# Synth_2.net
KiCad netlist of a schematic drawn in EAGLE
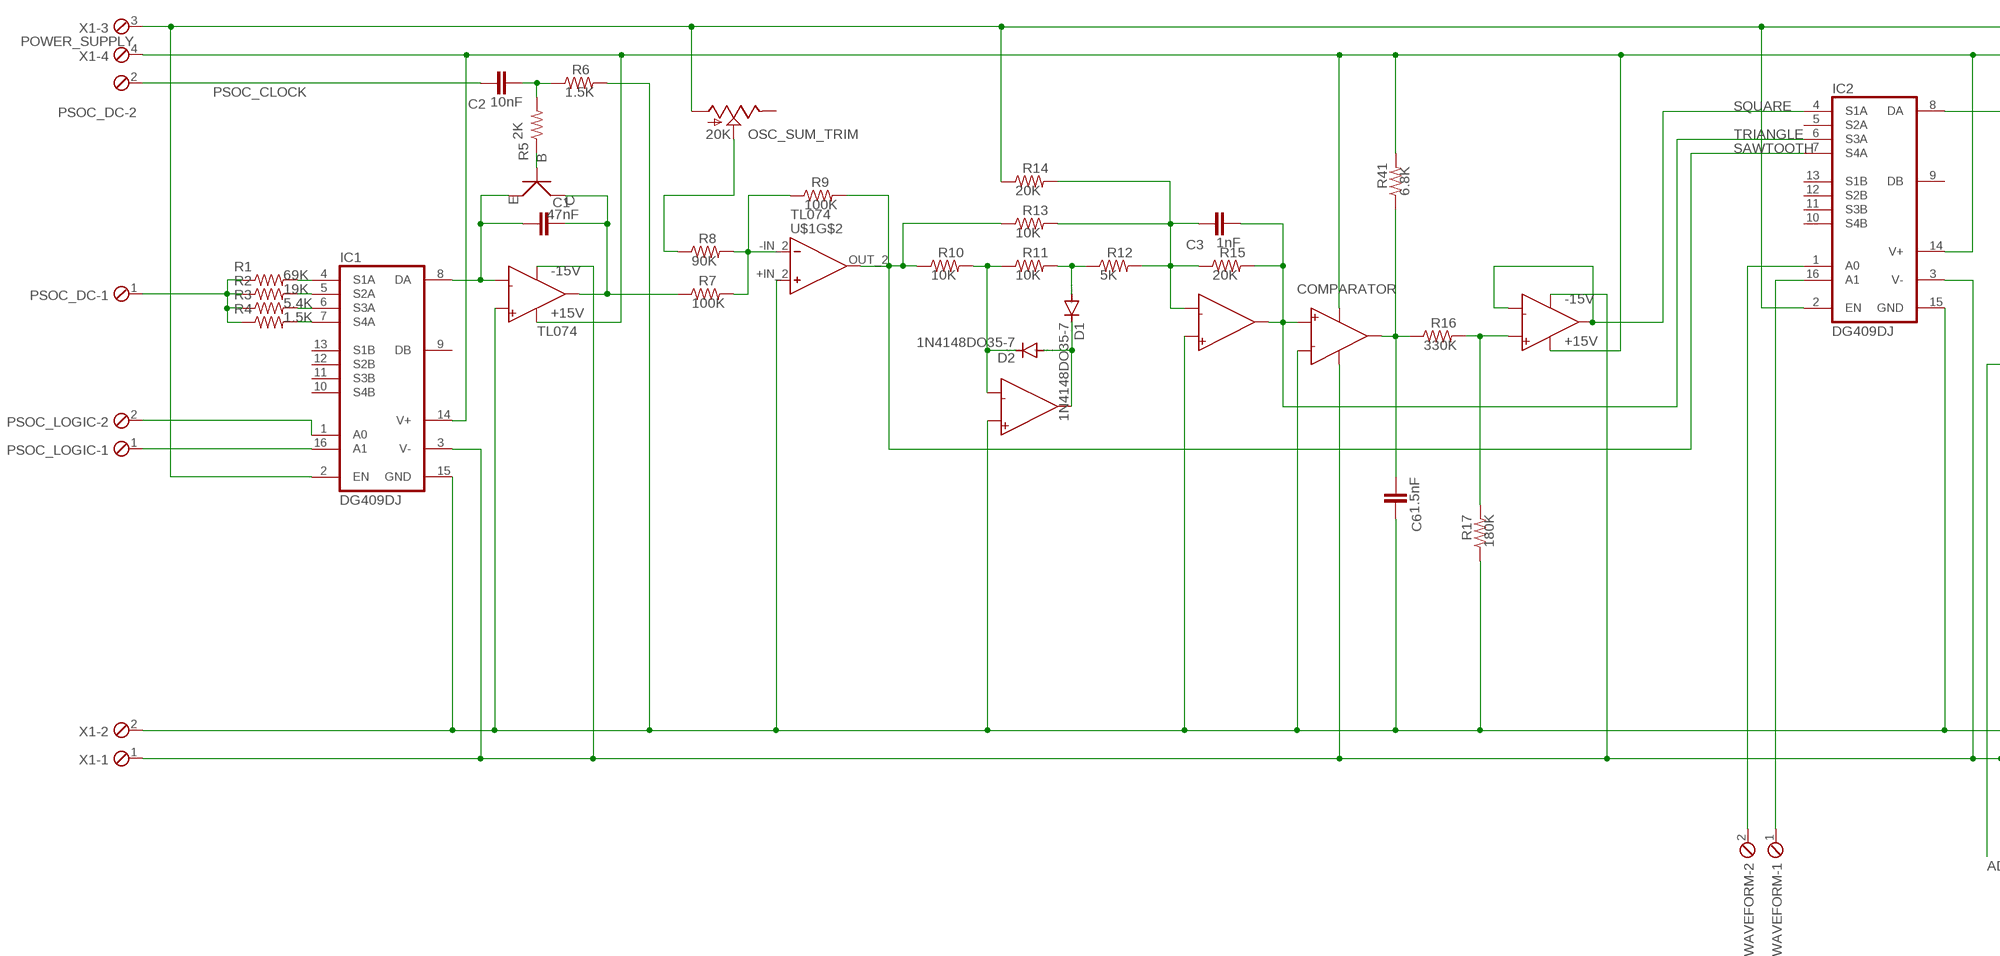
[diagram p0: schematic, sheet 1, part 1 of 2]
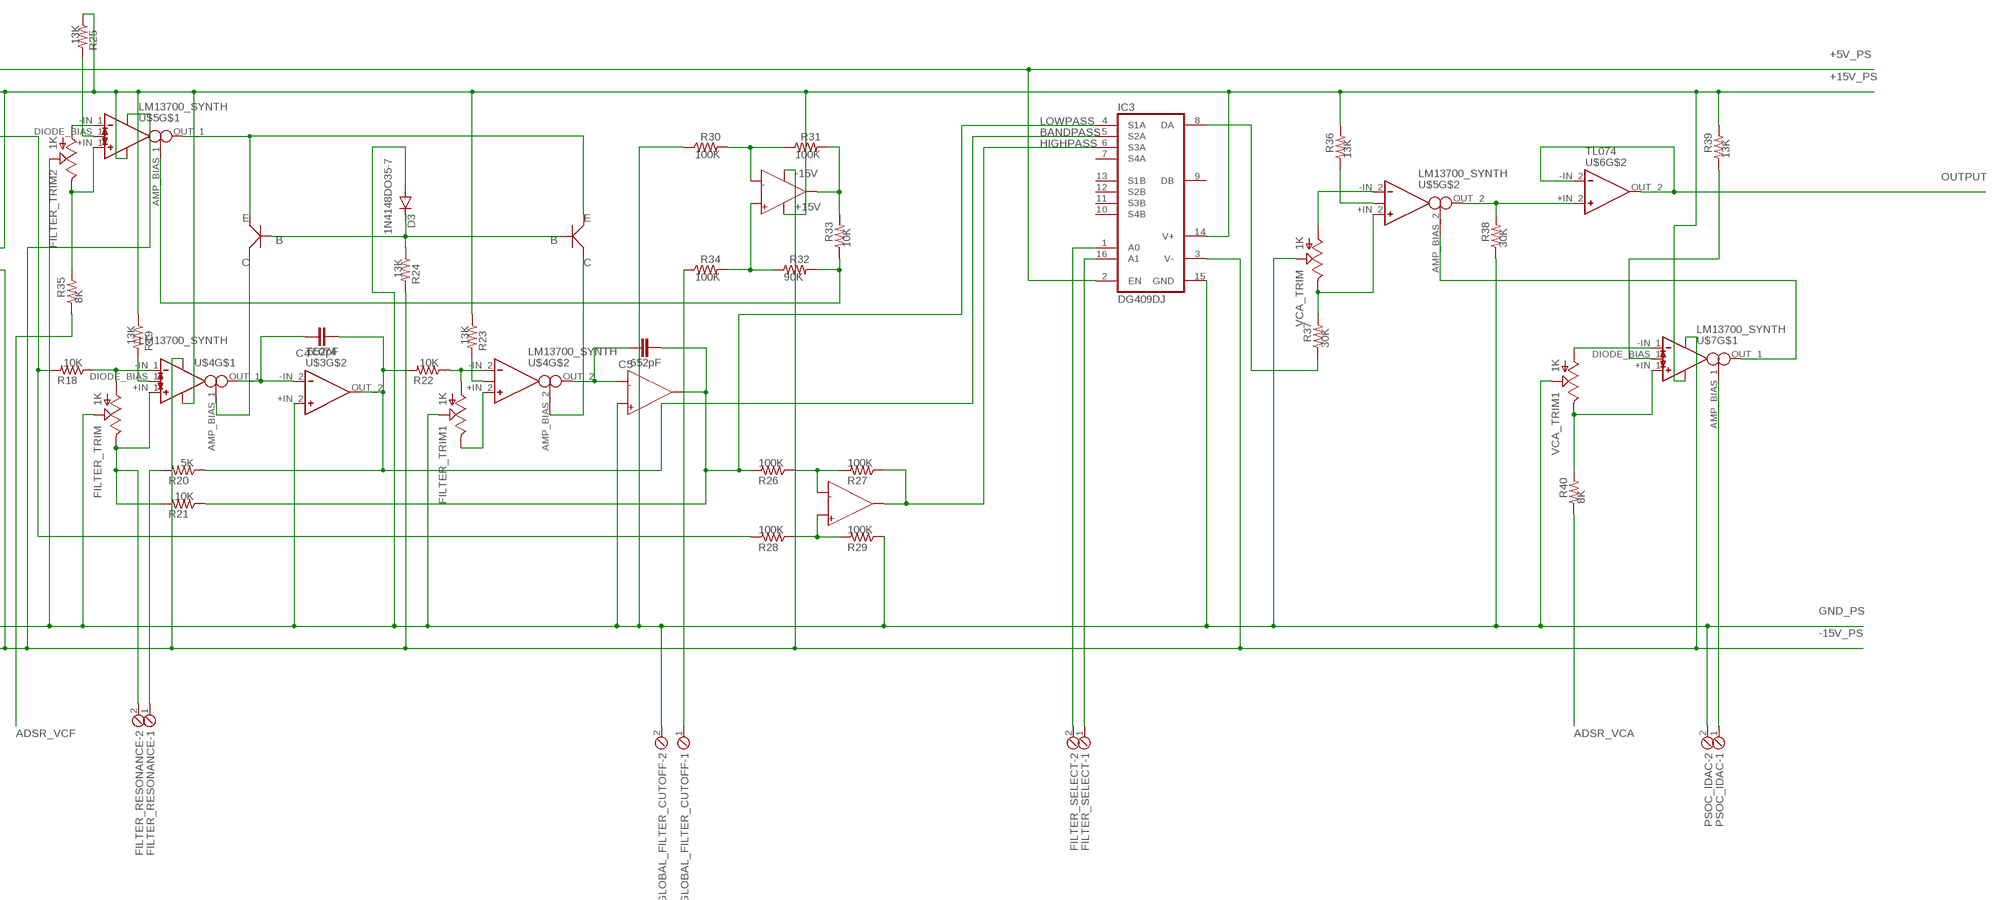
[diagram p1: schematic, sheet 1, part 2 of 2]

(export (version "E")
  (design (tool "Eeschema 10.0.6"))
  (components
    (comp (ref "C1")
      (value "C-EU025-024X044")
      (footprint "eagle-import:C025-024X044")
      (fields (field (name "SPICEPREFIX") "C") (field (name "SPICEPREFIX_1") "47nF"))
      (libsource (lib "eagle-import") (part "C-EU025-024X044"))
    )
    (comp (ref "C2")
      (value "C-EU025-024X044")
      (footprint "eagle-import:C025-024X044")
      (fields (field (name "SPICEPREFIX") "C") (field (name "SPICEPREFIX_1") "10nF"))
      (libsource (lib "eagle-import") (part "C-EU025-024X044"))
    )
    (comp (ref "C3")
      (value "C-EU025-024X044")
      (footprint "eagle-import:C025-024X044")
      (fields (field (name "SPICEPREFIX") "C") (field (name "SPICEPREFIX_1") "1nF"))
      (libsource (lib "eagle-import") (part "C-EU025-024X044"))
    )
    (comp (ref "C4")
      (value "C-EU025-024X044")
      (footprint "eagle-import:C025-024X044")
      (fields (field (name "SPICEPREFIX") "C") (field (name "SPICEPREFIX_1") "652pF"))
      (libsource (lib "eagle-import") (part "C-EU025-024X044"))
    )
    (comp (ref "C5")
      (value "C-EU025-024X044")
      (footprint "eagle-import:C025-024X044")
      (fields (field (name "SPICEPREFIX") "C") (field (name "SPICEPREFIX_1") "652pF"))
      (libsource (lib "eagle-import") (part "C-EU025-024X044"))
    )
    (comp (ref "C6")
      (value "C-EU025-024X044")
      (footprint "eagle-import:C025-024X044")
      (fields (field (name "SPICEPREFIX") "C") (field (name "SPICEPREFIX_1") "1.5nF"))
      (libsource (lib "eagle-import") (part "C-EU025-024X044"))
    )
    (comp (ref "D1")
      (value "1N4148DO35-7")
      (footprint "eagle-import:DO35-7")
      (libsource (lib "eagle-import") (part "1N4148DO35-7"))
    )
    (comp (ref "D2")
      (value "1N4148DO35-7")
      (footprint "eagle-import:DO35-7")
      (libsource (lib "eagle-import") (part "1N4148DO35-7"))
    )
    (comp (ref "D3")
      (value "1N4148DO35-7")
      (footprint "eagle-import:DO35-7")
      (libsource (lib "eagle-import") (part "1N4148DO35-7"))
    )
    (comp (ref "FILTER_RESONANCE")
      (value "MPT2")
      (footprint "eagle-import:2POL254")
      (libsource (lib "eagle-import") (part "MPT2"))
    )
    (comp (ref "FILTER_SELECT")
      (value "MPT2")
      (footprint "eagle-import:2POL254")
      (libsource (lib "eagle-import") (part "MPT2"))
    )
    (comp (ref "FILTER_TRIM")
      (value "TRIM_US-CT6")
      (footprint "eagle-import:CT6")
      (fields (field (name "POPULARITY") "2") (field (name "POPULARITY_1") "1K"))
      (libsource (lib "eagle-import") (part "TRIM_US-CT6"))
    )
    (comp (ref "FILTER_TRIM1")
      (value "TRIM_US-CT6")
      (footprint "eagle-import:CT6")
      (fields (field (name "POPULARITY") "2") (field (name "POPULARITY_1") "1K"))
      (libsource (lib "eagle-import") (part "TRIM_US-CT6"))
    )
    (comp (ref "FILTER_TRIM2")
      (value "TRIM_US-CT6")
      (footprint "eagle-import:CT6")
      (fields (field (name "POPULARITY") "2") (field (name "POPULARITY_1") "1K"))
      (libsource (lib "eagle-import") (part "TRIM_US-CT6"))
    )
    (comp (ref "GLOBAL_FILTER_CUTOFF")
      (value "MPT2")
      (footprint "eagle-import:2POL254")
      (libsource (lib "eagle-import") (part "MPT2"))
    )
    (comp (ref "IC1")
      (value "DG409DJ")
      (footprint "eagle-import:DIL16")
      (fields (field (name "MF") "INTERSIL"))
      (libsource (lib "eagle-import") (part "DG409DJ"))
    )
    (comp (ref "IC2")
      (value "DG409DJ")
      (footprint "eagle-import:DIL16")
      (fields (field (name "MF") "INTERSIL"))
      (libsource (lib "eagle-import") (part "DG409DJ"))
    )
    (comp (ref "IC3")
      (value "DG409DJ")
      (footprint "eagle-import:DIL16")
      (fields (field (name "MF") "INTERSIL"))
      (libsource (lib "eagle-import") (part "DG409DJ"))
    )
    (comp (ref "LM293")
      (value "LM293")
      (footprint "eagle-import:LM293")
      (libsource (lib "eagle-import") (part "LM293"))
    )
    (comp (ref "OSC_SUM_TRIM")
      (value "TRIM_US-CT6")
      (footprint "eagle-import:CT6")
      (fields (field (name "POPULARITY") "2") (field (name "POPULARITY_1") "20K"))
      (libsource (lib "eagle-import") (part "TRIM_US-CT6"))
    )
    (comp (ref "PSOC_DC")
      (value "MPT2")
      (footprint "eagle-import:2POL254")
      (libsource (lib "eagle-import") (part "MPT2"))
    )
    (comp (ref "PSOC_IDAC")
      (value "MPT2")
      (footprint "eagle-import:2POL254")
      (libsource (lib "eagle-import") (part "MPT2"))
    )
    (comp (ref "PSOC_LOGIC")
      (value "MPT2")
      (footprint "eagle-import:2POL254")
      (libsource (lib "eagle-import") (part "MPT2"))
    )
    (comp (ref "R1")
      (value "R-US_0204/7")
      (footprint "eagle-import:0204_7")
      (fields (field (name "SPICEPREFIX") "R") (field (name "SPICEPREFIX_1") "69K"))
      (libsource (lib "eagle-import") (part "R-US_0204/7"))
    )
    (comp (ref "R2")
      (value "R-US_0204/7")
      (footprint "eagle-import:0204_7")
      (fields (field (name "SPICEPREFIX") "R") (field (name "SPICEPREFIX_1") "19K"))
      (libsource (lib "eagle-import") (part "R-US_0204/7"))
    )
    (comp (ref "R3")
      (value "R-US_0204/7")
      (footprint "eagle-import:0204_7")
      (fields (field (name "SPICEPREFIX") "R") (field (name "SPICEPREFIX_1") "5.4K"))
      (libsource (lib "eagle-import") (part "R-US_0204/7"))
    )
    (comp (ref "R4")
      (value "R-US_0204/7")
      (footprint "eagle-import:0204_7")
      (fields (field (name "SPICEPREFIX") "R") (field (name "SPICEPREFIX_1") "1.5K"))
      (libsource (lib "eagle-import") (part "R-US_0204/7"))
    )
    (comp (ref "R5")
      (value "R-US_0204/7")
      (footprint "eagle-import:0204_7")
      (fields (field (name "SPICEPREFIX") "R") (field (name "SPICEPREFIX_1") "2K"))
      (libsource (lib "eagle-import") (part "R-US_0204/7"))
    )
    (comp (ref "R6")
      (value "R-US_0204/7")
      (footprint "eagle-import:0204_7")
      (fields (field (name "SPICEPREFIX") "R") (field (name "SPICEPREFIX_1") "1.5K"))
      (libsource (lib "eagle-import") (part "R-US_0204/7"))
    )
    (comp (ref "R7")
      (value "R-US_0204/7")
      (footprint "eagle-import:0204_7")
      (fields (field (name "SPICEPREFIX") "R") (field (name "SPICEPREFIX_1") "100K"))
      (libsource (lib "eagle-import") (part "R-US_0204/7"))
    )
    (comp (ref "R8")
      (value "R-US_0204/7")
      (footprint "eagle-import:0204_7")
      (fields (field (name "SPICEPREFIX") "R") (field (name "SPICEPREFIX_1") "90K"))
      (libsource (lib "eagle-import") (part "R-US_0204/7"))
    )
    (comp (ref "R9")
      (value "R-US_0204/7")
      (footprint "eagle-import:0204_7")
      (fields (field (name "SPICEPREFIX") "R") (field (name "SPICEPREFIX_1") "100K"))
      (libsource (lib "eagle-import") (part "R-US_0204/7"))
    )
    (comp (ref "R10")
      (value "R-US_0204/7")
      (footprint "eagle-import:0204_7")
      (fields (field (name "SPICEPREFIX") "R") (field (name "SPICEPREFIX_1") "10K"))
      (libsource (lib "eagle-import") (part "R-US_0204/7"))
    )
    (comp (ref "R11")
      (value "R-US_0204/7")
      (footprint "eagle-import:0204_7")
      (fields (field (name "SPICEPREFIX") "R") (field (name "SPICEPREFIX_1") "10K"))
      (libsource (lib "eagle-import") (part "R-US_0204/7"))
    )
    (comp (ref "R12")
      (value "R-US_0204/7")
      (footprint "eagle-import:0204_7")
      (fields (field (name "SPICEPREFIX") "R") (field (name "SPICEPREFIX_1") "5K"))
      (libsource (lib "eagle-import") (part "R-US_0204/7"))
    )
    (comp (ref "R13")
      (value "R-US_0204/7")
      (footprint "eagle-import:0204_7")
      (fields (field (name "SPICEPREFIX") "R") (field (name "SPICEPREFIX_1") "10K"))
      (libsource (lib "eagle-import") (part "R-US_0204/7"))
    )
    (comp (ref "R14")
      (value "R-US_0204/7")
      (footprint "eagle-import:0204_7")
      (fields (field (name "SPICEPREFIX") "R") (field (name "SPICEPREFIX_1") "20K"))
      (libsource (lib "eagle-import") (part "R-US_0204/7"))
    )
    (comp (ref "R15")
      (value "R-US_0204/7")
      (footprint "eagle-import:0204_7")
      (fields (field (name "SPICEPREFIX") "R") (field (name "SPICEPREFIX_1") "20K"))
      (libsource (lib "eagle-import") (part "R-US_0204/7"))
    )
    (comp (ref "R16")
      (value "R-US_0204/7")
      (footprint "eagle-import:0204_7")
      (fields (field (name "SPICEPREFIX") "R") (field (name "SPICEPREFIX_1") "330K"))
      (libsource (lib "eagle-import") (part "R-US_0204/7"))
    )
    (comp (ref "R17")
      (value "R-US_0204/7")
      (footprint "eagle-import:0204_7")
      (fields (field (name "SPICEPREFIX") "R") (field (name "SPICEPREFIX_1") "180K"))
      (libsource (lib "eagle-import") (part "R-US_0204/7"))
    )
    (comp (ref "R18")
      (value "R-US_0204/7")
      (footprint "eagle-import:0204_7")
      (fields (field (name "SPICEPREFIX") "R") (field (name "SPICEPREFIX_1") "10K"))
      (libsource (lib "eagle-import") (part "R-US_0204/7"))
    )
    (comp (ref "R19")
      (value "R-US_0204/7")
      (footprint "eagle-import:0204_7")
      (fields (field (name "SPICEPREFIX") "R") (field (name "SPICEPREFIX_1") "13K"))
      (libsource (lib "eagle-import") (part "R-US_0204/7"))
    )
    (comp (ref "R20")
      (value "R-US_0204/7")
      (footprint "eagle-import:0204_7")
      (fields (field (name "SPICEPREFIX") "R") (field (name "SPICEPREFIX_1") "5K"))
      (libsource (lib "eagle-import") (part "R-US_0204/7"))
    )
    (comp (ref "R21")
      (value "R-US_0204/7")
      (footprint "eagle-import:0204_7")
      (fields (field (name "SPICEPREFIX") "R") (field (name "SPICEPREFIX_1") "10K"))
      (libsource (lib "eagle-import") (part "R-US_0204/7"))
    )
    (comp (ref "R22")
      (value "R-US_0204/7")
      (footprint "eagle-import:0204_7")
      (fields (field (name "SPICEPREFIX") "R") (field (name "SPICEPREFIX_1") "10K"))
      (libsource (lib "eagle-import") (part "R-US_0204/7"))
    )
    (comp (ref "R23")
      (value "R-US_0204/7")
      (footprint "eagle-import:0204_7")
      (fields (field (name "SPICEPREFIX") "R") (field (name "SPICEPREFIX_1") "13K"))
      (libsource (lib "eagle-import") (part "R-US_0204/7"))
    )
    (comp (ref "R24")
      (value "R-US_0204/7")
      (footprint "eagle-import:0204_7")
      (fields (field (name "SPICEPREFIX") "R") (field (name "SPICEPREFIX_1") "13K"))
      (libsource (lib "eagle-import") (part "R-US_0204/7"))
    )
    (comp (ref "R25")
      (value "R-US_0204/7")
      (footprint "eagle-import:0204_7")
      (fields (field (name "SPICEPREFIX") "R") (field (name "SPICEPREFIX_1") "13K"))
      (libsource (lib "eagle-import") (part "R-US_0204/7"))
    )
    (comp (ref "R26")
      (value "R-US_0204/7")
      (footprint "eagle-import:0204_7")
      (fields (field (name "SPICEPREFIX") "R") (field (name "SPICEPREFIX_1") "100K"))
      (libsource (lib "eagle-import") (part "R-US_0204/7"))
    )
    (comp (ref "R27")
      (value "R-US_0204/7")
      (footprint "eagle-import:0204_7")
      (fields (field (name "SPICEPREFIX") "R") (field (name "SPICEPREFIX_1") "100K"))
      (libsource (lib "eagle-import") (part "R-US_0204/7"))
    )
    (comp (ref "R28")
      (value "R-US_0204/7")
      (footprint "eagle-import:0204_7")
      (fields (field (name "SPICEPREFIX") "R") (field (name "SPICEPREFIX_1") "100K"))
      (libsource (lib "eagle-import") (part "R-US_0204/7"))
    )
    (comp (ref "R29")
      (value "R-US_0204/7")
      (footprint "eagle-import:0204_7")
      (fields (field (name "SPICEPREFIX") "R") (field (name "SPICEPREFIX_1") "100K"))
      (libsource (lib "eagle-import") (part "R-US_0204/7"))
    )
    (comp (ref "R30")
      (value "R-US_0204/7")
      (footprint "eagle-import:0204_7")
      (fields (field (name "SPICEPREFIX") "R") (field (name "SPICEPREFIX_1") "100K"))
      (libsource (lib "eagle-import") (part "R-US_0204/7"))
    )
    (comp (ref "R31")
      (value "R-US_0204/7")
      (footprint "eagle-import:0204_7")
      (fields (field (name "SPICEPREFIX") "R") (field (name "SPICEPREFIX_1") "100K"))
      (libsource (lib "eagle-import") (part "R-US_0204/7"))
    )
    (comp (ref "R32")
      (value "R-US_0204/7")
      (footprint "eagle-import:0204_7")
      (fields (field (name "SPICEPREFIX") "R") (field (name "SPICEPREFIX_1") "90K"))
      (libsource (lib "eagle-import") (part "R-US_0204/7"))
    )
    (comp (ref "R33")
      (value "R-US_0204/7")
      (footprint "eagle-import:0204_7")
      (fields (field (name "SPICEPREFIX") "R") (field (name "SPICEPREFIX_1") "10K"))
      (libsource (lib "eagle-import") (part "R-US_0204/7"))
    )
    (comp (ref "R34")
      (value "R-US_0204/7")
      (footprint "eagle-import:0204_7")
      (fields (field (name "SPICEPREFIX") "R") (field (name "SPICEPREFIX_1") "100K"))
      (libsource (lib "eagle-import") (part "R-US_0204/7"))
    )
    (comp (ref "R35")
      (value "R-US_0204/7")
      (footprint "eagle-import:0204_7")
      (fields (field (name "SPICEPREFIX") "R") (field (name "SPICEPREFIX_1") "8K"))
      (libsource (lib "eagle-import") (part "R-US_0204/7"))
    )
    (comp (ref "R36")
      (value "R-US_0204/7")
      (footprint "eagle-import:0204_7")
      (fields (field (name "SPICEPREFIX") "R") (field (name "SPICEPREFIX_1") "13K"))
      (libsource (lib "eagle-import") (part "R-US_0204/7"))
    )
    (comp (ref "R37")
      (value "R-US_0204/7")
      (footprint "eagle-import:0204_7")
      (fields (field (name "SPICEPREFIX") "R") (field (name "SPICEPREFIX_1") "30K"))
      (libsource (lib "eagle-import") (part "R-US_0204/7"))
    )
    (comp (ref "R38")
      (value "R-US_0204/7")
      (footprint "eagle-import:0204_7")
      (fields (field (name "SPICEPREFIX") "R") (field (name "SPICEPREFIX_1") "30K"))
      (libsource (lib "eagle-import") (part "R-US_0204/7"))
    )
    (comp (ref "R39")
      (value "R-US_0204/7")
      (footprint "eagle-import:0204_7")
      (fields (field (name "SPICEPREFIX") "R") (field (name "SPICEPREFIX_1") "13K"))
      (libsource (lib "eagle-import") (part "R-US_0204/7"))
    )
    (comp (ref "R40")
      (value "R-US_0204/7")
      (footprint "eagle-import:0204_7")
      (fields (field (name "SPICEPREFIX") "R") (field (name "SPICEPREFIX_1") "8K"))
      (libsource (lib "eagle-import") (part "R-US_0204/7"))
    )
    (comp (ref "R41")
      (value "R-US_0204/7")
      (footprint "eagle-import:0204_7")
      (fields (field (name "SPICEPREFIX") "R") (field (name "SPICEPREFIX_1") "6.8K"))
      (libsource (lib "eagle-import") (part "R-US_0204/7"))
    )
    (comp (ref "U$1")
      (value "TL074")
      (footprint "eagle-import:TL074")
      (libsource (lib "eagle-import") (part "TL074"))
    )
    (comp (ref "U$2")
      (value "MPQ2907A")
      (footprint "eagle-import:MPQ2907A")
      (libsource (lib "eagle-import") (part "MPQ2907A"))
    )
    (comp (ref "U$3")
      (value "TL074")
      (footprint "eagle-import:TL074")
      (libsource (lib "eagle-import") (part "TL074"))
    )
    (comp (ref "U$4")
      (value "LM13700_SYNTH")
      (footprint "eagle-import:LM13700_SYNTH")
      (libsource (lib "eagle-import") (part "LM13700_SYNTH"))
    )
    (comp (ref "U$5")
      (value "LM13700_SYNTH")
      (footprint "eagle-import:LM13700_SYNTH")
      (libsource (lib "eagle-import") (part "LM13700_SYNTH"))
    )
    (comp (ref "U$6")
      (value "TL074")
      (footprint "eagle-import:TL074")
      (libsource (lib "eagle-import") (part "TL074"))
    )
    (comp (ref "U$7")
      (value "LM13700_SYNTH")
      (footprint "eagle-import:LM13700_SYNTH")
      (libsource (lib "eagle-import") (part "LM13700_SYNTH"))
    )
    (comp (ref "VCA_TRIM")
      (value "TRIM_US-CT6")
      (footprint "eagle-import:CT6")
      (fields (field (name "POPULARITY") "2") (field (name "POPULARITY_1") "1K"))
      (libsource (lib "eagle-import") (part "TRIM_US-CT6"))
    )
    (comp (ref "VCA_TRIM1")
      (value "TRIM_US-CT6")
      (footprint "eagle-import:CT6")
      (fields (field (name "POPULARITY") "2") (field (name "POPULARITY_1") "1K"))
      (libsource (lib "eagle-import") (part "TRIM_US-CT6"))
    )
    (comp (ref "WAVEFORM")
      (value "MPT2")
      (footprint "eagle-import:2POL254")
      (libsource (lib "eagle-import") (part "MPT2"))
    )
    (comp (ref "X1")
      (value "POWER_SUPPLY")
      (footprint "eagle-import:4POL254")
      (libsource (lib "eagle-import") (part "MPT4"))
    )
  )
  (nets
    (net (code "1") (name "/+5V_PS") (class "Default")
      (node (ref "IC1") (pin "2") (pinfunction "EN_2") (pintype "input"))
      (node (ref "IC2") (pin "2") (pinfunction "EN_2") (pintype "input"))
      (node (ref "IC3") (pin "2") (pinfunction "EN_2") (pintype "input"))
      (node (ref "OSC_SUM_TRIM") (pin "A") (pinfunction "A_A") (pintype "passive"))
      (node (ref "R14") (pin "1") (pinfunction "1_1") (pintype "passive"))
      (node (ref "X1") (pin "3") (pinfunction "1_3") (pintype "passive"))
    )
    (net (code "2") (name "/+15V_PS") (class "Default")
      (node (ref "IC1") (pin "14") (pinfunction "V+_14") (pintype "power_in"))
      (node (ref "IC2") (pin "14") (pinfunction "V+_14") (pintype "power_in"))
      (node (ref "IC3") (pin "14") (pinfunction "V+_14") (pintype "power_in"))
      (node (ref "LM293") (pin "VCC") (pinfunction "VCC_VCC") (pintype "power_in"))
      (node (ref "R19") (pin "1") (pinfunction "1_1") (pintype "passive"))
      (node (ref "R23") (pin "1") (pinfunction "1_1") (pintype "passive"))
      (node (ref "R25") (pin "1") (pinfunction "1_1") (pintype "passive"))
      (node (ref "R36") (pin "2") (pinfunction "2_2") (pintype "passive"))
      (node (ref "R39") (pin "2") (pinfunction "2_2") (pintype "passive"))
      (node (ref "R41") (pin "2") (pinfunction "2_2") (pintype "passive"))
      (node (ref "U$1") (pin "VCC+") (pinfunction "VCC+_VCC+") (pintype "power_in"))
      (node (ref "U$3") (pin "VCC+") (pinfunction "VCC+_VCC+") (pintype "power_in"))
      (node (ref "U$4") (pin "+V") (pinfunction "+V_+V") (pintype "power_in"))
      (node (ref "U$5") (pin "+V") (pinfunction "+V_+V") (pintype "power_in"))
      (node (ref "U$6") (pin "VCC+") (pinfunction "VCC+_VCC+") (pintype "power_in"))
      (node (ref "U$7") (pin "+V") (pinfunction "+V_+V") (pintype "power_in"))
      (node (ref "X1") (pin "4") (pinfunction "1_4") (pintype "passive"))
    )
    (net (code "3") (name "/-15V_PS") (class "Default")
      (node (ref "IC1") (pin "3") (pinfunction "V-_3") (pintype "power_in"))
      (node (ref "IC2") (pin "3") (pinfunction "V-_3") (pintype "power_in"))
      (node (ref "IC3") (pin "3") (pinfunction "V-_3") (pintype "power_in"))
      (node (ref "LM293") (pin "GND") (pinfunction "GND_GND") (pintype "input"))
      (node (ref "R24") (pin "2") (pinfunction "2_2") (pintype "passive"))
      (node (ref "U$1") (pin "VCC-") (pinfunction "VCC-_VCC-") (pintype "power_in"))
      (node (ref "U$3") (pin "VCC-") (pinfunction "VCC-_VCC-") (pintype "power_in"))
      (node (ref "U$4") (pin "-V") (pinfunction "-V_-V") (pintype "power_in"))
      (node (ref "U$5") (pin "-V") (pinfunction "-V_-V") (pintype "power_in"))
      (node (ref "U$6") (pin "VCC-") (pinfunction "VCC-_VCC-") (pintype "power_in"))
      (node (ref "U$7") (pin "-V") (pinfunction "-V_-V") (pintype "power_in"))
      (node (ref "X1") (pin "1") (pinfunction "1_1") (pintype "passive"))
    )
    (net (code "4") (name "/ADSR_VCA") (class "Default")
      (node (ref "R40") (pin "2") (pinfunction "2_2") (pintype "passive"))
      (node (ref "U$7") (pin "+IN_1") (pinfunction "+IN_1_+IN_1") (pintype "input"))
      (node (ref "VCA_TRIM1") (pin "E") (pinfunction "E_E") (pintype "passive"))
    )
    (net (code "5") (name "/ADSR_VCF") (class "Default")
      (node (ref "R35") (pin "1") (pinfunction "1_1") (pintype "passive"))
    )
    (net (code "6") (name "/BANDPASS") (class "Default")
      (node (ref "C4") (pin "2") (pinfunction "2_2") (pintype "passive"))
      (node (ref "IC3") (pin "5") (pinfunction "S2A_5") (pintype "passive"))
      (node (ref "R20") (pin "1") (pinfunction "1_1") (pintype "passive"))
      (node (ref "R22") (pin "2") (pinfunction "2_2") (pintype "passive"))
      (node (ref "U$3") (pin "OUT_2") (pinfunction "OUT_2_OUT_2") (pintype "output"))
    )
    (net (code "7") (name "/COMPARATOR") (class "Default")
      (node (ref "C6") (pin "2") (pinfunction "2_2") (pintype "passive"))
      (node (ref "LM293") (pin "OUT_1") (pinfunction "OUT_1_OUT_1") (pintype "output"))
      (node (ref "R16") (pin "1") (pinfunction "1_1") (pintype "passive"))
      (node (ref "R41") (pin "1") (pinfunction "1_1") (pintype "passive"))
    )
    (net (code "8") (name "/GND_PS") (class "Default")
      (node (ref "C6") (pin "1") (pinfunction "1_1") (pintype "passive"))
      (node (ref "D3") (pin "A") (pinfunction "A_A") (pintype "passive"))
      (node (ref "FILTER_TRIM") (pin "S") (pinfunction "S_S") (pintype "passive"))
      (node (ref "FILTER_TRIM1") (pin "S") (pinfunction "S_S") (pintype "passive"))
      (node (ref "FILTER_TRIM2") (pin "S") (pinfunction "S_S") (pintype "passive"))
      (node (ref "GLOBAL_FILTER_CUTOFF") (pin "2") (pinfunction "1_2") (pintype "passive"))
      (node (ref "IC1") (pin "15") (pinfunction "GND_15") (pintype "power_in"))
      (node (ref "IC2") (pin "15") (pinfunction "GND_15") (pintype "power_in"))
      (node (ref "IC3") (pin "15") (pinfunction "GND_15") (pintype "power_in"))
      (node (ref "LM293") (pin "-IN_1") (pinfunction "-IN_1_-IN_1") (pintype "input"))
      (node (ref "PSOC_IDAC") (pin "2") (pinfunction "1_2") (pintype "passive"))
      (node (ref "R17") (pin "1") (pinfunction "1_1") (pintype "passive"))
      (node (ref "R29") (pin "1") (pinfunction "1_1") (pintype "passive"))
      (node (ref "R30") (pin "1") (pinfunction "1_1") (pintype "passive"))
      (node (ref "R38") (pin "1") (pinfunction "1_1") (pintype "passive"))
      (node (ref "R6") (pin "2") (pinfunction "2_2") (pintype "passive"))
      (node (ref "U$1") (pin "+IN_1") (pinfunction "+IN_1_+IN_1") (pintype "input"))
      (node (ref "U$1") (pin "+IN_2") (pinfunction "+IN_2_+IN_2") (pintype "input"))
      (node (ref "U$1") (pin "+IN_3") (pinfunction "+IN_3_+IN_3") (pintype "input"))
      (node (ref "U$1") (pin "+IN_4") (pinfunction "+IN_4_+IN_4") (pintype "input"))
      (node (ref "U$3") (pin "+IN_2") (pinfunction "+IN_2_+IN_2") (pintype "input"))
      (node (ref "U$3") (pin "+IN_4") (pinfunction "+IN_4_+IN_4") (pintype "input"))
      (node (ref "VCA_TRIM") (pin "S") (pinfunction "S_S") (pintype "passive"))
      (node (ref "VCA_TRIM1") (pin "S") (pinfunction "S_S") (pintype "passive"))
      (node (ref "X1") (pin "2") (pinfunction "1_2") (pintype "passive"))
    )
    (net (code "9") (name "/HIGHPASS") (class "Default")
      (node (ref "IC3") (pin "6") (pinfunction "S3A_6") (pintype "passive"))
      (node (ref "R27") (pin "1") (pinfunction "1_1") (pintype "passive"))
      (node (ref "U$3") (pin "OUT_3") (pinfunction "OUT_3_OUT_3") (pintype "output"))
    )
    (net (code "10") (name "/LOWPASS") (class "Default")
      (node (ref "C5") (pin "2") (pinfunction "2_2") (pintype "passive"))
      (node (ref "IC3") (pin "4") (pinfunction "S1A_4") (pintype "passive"))
      (node (ref "R21") (pin "1") (pinfunction "1_1") (pintype "passive"))
      (node (ref "R26") (pin "2") (pinfunction "2_2") (pintype "passive"))
      (node (ref "U$3") (pin "OUT_4") (pinfunction "OUT_4_OUT_4") (pintype "input"))
    )
    (net (code "11") (name "/OUTPUT") (class "Default")
      (node (ref "U$6") (pin "-IN_2") (pinfunction "-IN_2_-IN_2") (pintype "input"))
      (node (ref "U$6") (pin "OUT_2") (pinfunction "OUT_2_OUT_2") (pintype "output"))
    )
    (net (code "12") (name "/PSOC_CLOCK") (class "Default")
      (node (ref "C2") (pin "1") (pinfunction "1_1") (pintype "passive"))
      (node (ref "PSOC_DC") (pin "2") (pinfunction "1_2") (pintype "passive"))
    )
    (net (code "13") (name "/SAWTOOTH") (class "Default")
      (node (ref "IC2") (pin "7") (pinfunction "S4A_7") (pintype "passive"))
      (node (ref "R10") (pin "1") (pinfunction "1_1") (pintype "passive"))
      (node (ref "R13") (pin "1") (pinfunction "1_1") (pintype "passive"))
      (node (ref "R9") (pin "2") (pinfunction "2_2") (pintype "passive"))
      (node (ref "U$1") (pin "OUT_2") (pinfunction "OUT_2_OUT_2") (pintype "output"))
    )
    (net (code "14") (name "/SQUARE") (class "Default")
      (node (ref "IC2") (pin "4") (pinfunction "S1A_4") (pintype "passive"))
      (node (ref "U$3") (pin "-IN_1") (pinfunction "-IN_1_-IN_1") (pintype "input"))
      (node (ref "U$3") (pin "OUT_1") (pinfunction "OUT_1_OUT_1") (pintype "output"))
    )
    (net (code "15") (name "/TL074") (class "Default")
      (node (ref "C1") (pin "1") (pinfunction "1_1") (pintype "passive"))
      (node (ref "IC1") (pin "8") (pinfunction "DA_8") (pintype "passive"))
      (node (ref "U$1") (pin "-IN_1") (pinfunction "-IN_1_-IN_1") (pintype "input"))
      (node (ref "U$2") (pin "Q1_E") (pinfunction "E_Q1_E") (pintype "bidirectional"))
    )
    (net (code "16") (name "/TRIANGLE") (class "Default")
      (node (ref "C3") (pin "2") (pinfunction "2_2") (pintype "passive"))
      (node (ref "IC2") (pin "6") (pinfunction "S3A_6") (pintype "passive"))
      (node (ref "LM293") (pin "+IN_1") (pinfunction "+IN_1_+IN_1") (pintype "input"))
      (node (ref "R15") (pin "2") (pinfunction "2_2") (pintype "passive"))
      (node (ref "U$1") (pin "OUT_4") (pinfunction "OUT_4_OUT_4") (pintype "input"))
    )
    (net (code "17") (name "Net-(C2-Pad2)") (class "Default")
      (node (ref "C2") (pin "2") (pinfunction "2_2") (pintype "passive"))
      (node (ref "R5") (pin "2") (pinfunction "2_2") (pintype "passive"))
      (node (ref "R6") (pin "1") (pinfunction "1_1") (pintype "passive"))
    )
    (net (code "18") (name "Net-(C3-Pad1)") (class "Default")
      (node (ref "C3") (pin "1") (pinfunction "1_1") (pintype "passive"))
      (node (ref "R12") (pin "2") (pinfunction "2_2") (pintype "passive"))
      (node (ref "R13") (pin "2") (pinfunction "2_2") (pintype "passive"))
      (node (ref "R14") (pin "2") (pinfunction "2_2") (pintype "passive"))
      (node (ref "R15") (pin "1") (pinfunction "1_1") (pintype "passive"))
      (node (ref "U$1") (pin "-IN_4") (pinfunction "-IN_4_-IN_4") (pintype "input"))
    )
    (net (code "19") (name "Net-(C4-Pad1)") (class "Default")
      (node (ref "C4") (pin "1") (pinfunction "1_1") (pintype "passive"))
      (node (ref "U$3") (pin "-IN_2") (pinfunction "-IN_2_-IN_2") (pintype "input"))
      (node (ref "U$4") (pin "OUT_1") (pinfunction "OUT_1_OUT_1") (pintype "output"))
    )
    (net (code "20") (name "Net-(C5-Pad1)") (class "Default")
      (node (ref "C5") (pin "1") (pinfunction "1_1") (pintype "passive"))
      (node (ref "U$3") (pin "-IN_4") (pinfunction "-IN_4_-IN_4") (pintype "input"))
      (node (ref "U$4") (pin "OUT_2") (pinfunction "OUT_2_OUT_2") (pintype "output"))
    )
    (net (code "21") (name "Net-(D1-PadA)") (class "Default")
      (node (ref "D1") (pin "A") (pinfunction "A_A") (pintype "passive"))
      (node (ref "R11") (pin "2") (pinfunction "2_2") (pintype "passive"))
      (node (ref "R12") (pin "1") (pinfunction "1_1") (pintype "passive"))
    )
    (net (code "22") (name "Net-(D1-PadC)") (class "Default")
      (node (ref "D1") (pin "C") (pinfunction "C_C") (pintype "passive"))
      (node (ref "D2") (pin "A") (pinfunction "A_A") (pintype "passive"))
      (node (ref "U$1") (pin "OUT_3") (pinfunction "OUT_3_OUT_3") (pintype "output"))
    )
    (net (code "23") (name "Net-(D2-PadC)") (class "Default")
      (node (ref "D2") (pin "C") (pinfunction "C_C") (pintype "passive"))
      (node (ref "R10") (pin "2") (pinfunction "2_2") (pintype "passive"))
      (node (ref "R11") (pin "1") (pinfunction "1_1") (pintype "passive"))
      (node (ref "U$1") (pin "-IN_3") (pinfunction "-IN_3_-IN_3") (pintype "input"))
    )
    (net (code "24") (name "Net-(FILTER_RESONANCE-Pad1)") (class "Default")
      (node (ref "FILTER_RESONANCE") (pin "1") (pinfunction "1_1") (pintype "passive"))
      (node (ref "R20") (pin "2") (pinfunction "2_2") (pintype "passive"))
    )
    (net (code "25") (name "Net-(FILTER_RESONANCEB-1)") (class "Default")
      (node (ref "FILTER_RESONANCE") (pin "2") (pinfunction "1_2") (pintype "passive"))
      (node (ref "FILTER_TRIM") (pin "E") (pinfunction "E_E") (pintype "passive"))
      (node (ref "R21") (pin "2") (pinfunction "2_2") (pintype "passive"))
      (node (ref "U$4") (pin "+IN_1") (pinfunction "+IN_1_+IN_1") (pintype "input"))
    )
    (net (code "26") (name "Net-(FILTER_SELECTB-1)") (class "Default")
      (node (ref "FILTER_SELECT") (pin "2") (pinfunction "1_2") (pintype "passive"))
      (node (ref "IC3") (pin "1") (pinfunction "A0_1") (pintype "input"))
    )
    (net (code "27") (name "Net-(FILTER_TRIM-PadA)") (class "Default")
      (node (ref "FILTER_TRIM") (pin "A") (pinfunction "A_A") (pintype "passive"))
      (node (ref "R18") (pin "1") (pinfunction "1_1") (pintype "passive"))
      (node (ref "U$4") (pin "-IN_1") (pinfunction "-IN_1_-IN_1") (pintype "input"))
    )
    (net (code "28") (name "Net-(FILTER_TRIM1-PadA)") (class "Default")
      (node (ref "FILTER_TRIM1") (pin "A") (pinfunction "A_A") (pintype "passive"))
      (node (ref "R22") (pin "1") (pinfunction "1_1") (pintype "passive"))
      (node (ref "U$4") (pin "-IN_2") (pinfunction "-IN_2_-IN_2") (pintype "input"))
    )
    (net (code "29") (name "Net-(FILTER_TRIM1-PadE)") (class "Default")
      (node (ref "FILTER_TRIM1") (pin "E") (pinfunction "E_E") (pintype "passive"))
      (node (ref "U$4") (pin "+IN_2") (pinfunction "+IN_2_+IN_2") (pintype "input"))
    )
    (net (code "30") (name "Net-(FILTER_TRIM2-PadA)") (class "Default")
      (node (ref "FILTER_TRIM2") (pin "A") (pinfunction "A_A") (pintype "passive"))
      (node (ref "U$5") (pin "-IN_1") (pinfunction "-IN_1_-IN_1") (pintype "input"))
    )
    (net (code "31") (name "Net-(FILTER_TRIM2-PadE)") (class "Default")
      (node (ref "FILTER_TRIM2") (pin "E") (pinfunction "E_E") (pintype "passive"))
      (node (ref "R35") (pin "2") (pinfunction "2_2") (pintype "passive"))
      (node (ref "U$5") (pin "+IN_1") (pinfunction "+IN_1_+IN_1") (pintype "input"))
    )
    (net (code "32") (name "Net-(GLOBAL_FILTER_CUTOFF-Pad1)") (class "Default")
      (node (ref "GLOBAL_FILTER_CUTOFF") (pin "1") (pinfunction "1_1") (pintype "passive"))
      (node (ref "R34") (pin "1") (pinfunction "1_1") (pintype "passive"))
    )
    (net (code "33") (name "Net-(IC1-A0)") (class "Default")
      (node (ref "IC1") (pin "1") (pinfunction "A0_1") (pintype "input"))
      (node (ref "PSOC_LOGIC") (pin "2") (pinfunction "1_2") (pintype "passive"))
    )
    (net (code "34") (name "Net-(IC1-A1)") (class "Default")
      (node (ref "IC1") (pin "16") (pinfunction "A1_16") (pintype "input"))
      (node (ref "PSOC_LOGIC") (pin "1") (pinfunction "1_1") (pintype "passive"))
    )
    (net (code "35") (name "Net-(IC1-S1A)") (class "Default")
      (node (ref "IC1") (pin "4") (pinfunction "S1A_4") (pintype "passive"))
      (node (ref "R1") (pin "2") (pinfunction "2_2") (pintype "passive"))
    )
    (net (code "36") (name "Net-(IC1-S2A)") (class "Default")
      (node (ref "IC1") (pin "5") (pinfunction "S2A_5") (pintype "passive"))
      (node (ref "R2") (pin "2") (pinfunction "2_2") (pintype "passive"))
    )
    (net (code "37") (name "Net-(IC1-S3A)") (class "Default")
      (node (ref "IC1") (pin "6") (pinfunction "S3A_6") (pintype "passive"))
      (node (ref "R3") (pin "2") (pinfunction "2_2") (pintype "passive"))
    )
    (net (code "38") (name "Net-(IC1-S4A)") (class "Default")
      (node (ref "IC1") (pin "7") (pinfunction "S4A_7") (pintype "passive"))
      (node (ref "R4") (pin "2") (pinfunction "2_2") (pintype "passive"))
    )
    (net (code "39") (name "Net-(IC2-A0)") (class "Default")
      (node (ref "IC2") (pin "1") (pinfunction "A0_1") (pintype "input"))
      (node (ref "WAVEFORM") (pin "2") (pinfunction "1_2") (pintype "passive"))
    )
    (net (code "40") (name "Net-(IC2-A1)") (class "Default")
      (node (ref "IC2") (pin "16") (pinfunction "A1_16") (pintype "input"))
      (node (ref "WAVEFORM") (pin "1") (pinfunction "1_1") (pintype "passive"))
    )
    (net (code "41") (name "Net-(IC2-DA)") (class "Default")
      (node (ref "IC2") (pin "8") (pinfunction "DA_8") (pintype "passive"))
      (node (ref "R18") (pin "2") (pinfunction "2_2") (pintype "passive"))
      (node (ref "R28") (pin "2") (pinfunction "2_2") (pintype "passive"))
    )
    (net (code "42") (name "Net-(IC3-A1)") (class "Default")
      (node (ref "FILTER_SELECT") (pin "1") (pinfunction "1_1") (pintype "passive"))
      (node (ref "IC3") (pin "16") (pinfunction "A1_16") (pintype "input"))
    )
    (net (code "43") (name "Net-(IC3-DA)") (class "Default")
      (node (ref "IC3") (pin "8") (pinfunction "DA_8") (pintype "passive"))
      (node (ref "R37") (pin "1") (pinfunction "1_1") (pintype "passive"))
    )
    (net (code "44") (name "Net-(OSC_SUM_TRIM-PadS)") (class "Default")
      (node (ref "OSC_SUM_TRIM") (pin "S") (pinfunction "S_S") (pintype "passive"))
      (node (ref "R8") (pin "1") (pinfunction "1_1") (pintype "passive"))
    )
    (net (code "45") (name "Net-(PSOC_DC-Pad1)") (class "Default")
      (node (ref "PSOC_DC") (pin "1") (pinfunction "1_1") (pintype "passive"))
      (node (ref "R1") (pin "1") (pinfunction "1_1") (pintype "passive"))
      (node (ref "R2") (pin "1") (pinfunction "1_1") (pintype "passive"))
      (node (ref "R3") (pin "1") (pinfunction "1_1") (pintype "passive"))
      (node (ref "R4") (pin "1") (pinfunction "1_1") (pintype "passive"))
    )
    (net (code "46") (name "Net-(PSOC_IDAC-Pad1)") (class "Default")
      (node (ref "PSOC_IDAC") (pin "1") (pinfunction "1_1") (pintype "passive"))
      (node (ref "U$7") (pin "AMP_BIAS_1") (pinfunction "AMP_BIAS_1_AMP_BIAS_1") (pintype "input"))
    )
    (net (code "47") (name "Net-(R7-Pad2)") (class "Default")
      (node (ref "R7") (pin "2") (pinfunction "2_2") (pintype "passive"))
      (node (ref "R8") (pin "2") (pinfunction "2_2") (pintype "passive"))
      (node (ref "R9") (pin "1") (pinfunction "1_1") (pintype "passive"))
      (node (ref "U$1") (pin "-IN_2") (pinfunction "-IN_2_-IN_2") (pintype "input"))
    )
    (net (code "48") (name "Net-(R16-Pad2)") (class "Default")
      (node (ref "R16") (pin "2") (pinfunction "2_2") (pintype "passive"))
      (node (ref "R17") (pin "2") (pinfunction "2_2") (pintype "passive"))
      (node (ref "U$3") (pin "+IN_1") (pinfunction "+IN_1_+IN_1") (pintype "input"))
    )
    (net (code "49") (name "Net-(R19-Pad2)") (class "Default")
      (node (ref "R19") (pin "2") (pinfunction "2_2") (pintype "passive"))
      (node (ref "U$4") (pin "DIODE_BIAS_1") (pinfunction "DIODE_BIAS_1_DIODE_BIAS_1") (pintype "input"))
    )
    (net (code "50") (name "Net-(R23-Pad2)") (class "Default")
      (node (ref "R23") (pin "2") (pinfunction "2_2") (pintype "passive"))
      (node (ref "U$4") (pin "DIODE_BIAS_2") (pinfunction "DIODE_BIAS_2_DIODE_BIAS_2") (pintype "input"))
    )
    (net (code "51") (name "Net-(R25-Pad2)") (class "Default")
      (node (ref "R25") (pin "2") (pinfunction "2_2") (pintype "passive"))
      (node (ref "U$5") (pin "DIODE_BIAS_1") (pinfunction "DIODE_BIAS_1_DIODE_BIAS_1") (pintype "input"))
    )
    (net (code "52") (name "Net-(R26-Pad1)") (class "Default")
      (node (ref "R26") (pin "1") (pinfunction "1_1") (pintype "passive"))
      (node (ref "R27") (pin "2") (pinfunction "2_2") (pintype "passive"))
      (node (ref "U$3") (pin "-IN_3") (pinfunction "-IN_3_-IN_3") (pintype "input"))
    )
    (net (code "53") (name "Net-(R28-Pad1)") (class "Default")
      (node (ref "R28") (pin "1") (pinfunction "1_1") (pintype "passive"))
      (node (ref "R29") (pin "2") (pinfunction "2_2") (pintype "passive"))
      (node (ref "U$3") (pin "+IN_3") (pinfunction "+IN_3_+IN_3") (pintype "input"))
    )
    (net (code "54") (name "Net-(R30-Pad2)") (class "Default")
      (node (ref "R30") (pin "2") (pinfunction "2_2") (pintype "passive"))
      (node (ref "R31") (pin "1") (pinfunction "1_1") (pintype "passive"))
      (node (ref "U$6") (pin "-IN_1") (pinfunction "-IN_1_-IN_1") (pintype "input"))
    )
    (net (code "55") (name "Net-(R31-Pad2)") (class "Default")
      (node (ref "R31") (pin "2") (pinfunction "2_2") (pintype "passive"))
      (node (ref "R33") (pin "2") (pinfunction "2_2") (pintype "passive"))
      (node (ref "U$6") (pin "OUT_1") (pinfunction "OUT_1_OUT_1") (pintype "output"))
    )
    (net (code "56") (name "Net-(R32-Pad1)") (class "Default")
      (node (ref "R32") (pin "1") (pinfunction "1_1") (pintype "passive"))
      (node (ref "R34") (pin "2") (pinfunction "2_2") (pintype "passive"))
      (node (ref "U$6") (pin "+IN_1") (pinfunction "+IN_1_+IN_1") (pintype "input"))
    )
    (net (code "57") (name "Net-(R32-Pad2)") (class "Default")
      (node (ref "R32") (pin "2") (pinfunction "2_2") (pintype "passive"))
      (node (ref "R33") (pin "1") (pinfunction "1_1") (pintype "passive"))
      (node (ref "U$5") (pin "AMP_BIAS_1") (pinfunction "AMP_BIAS_1_AMP_BIAS_1") (pintype "input"))
    )
    (net (code "58") (name "Net-(R36-Pad1)") (class "Default")
      (node (ref "R36") (pin "1") (pinfunction "1_1") (pintype "passive"))
      (node (ref "U$5") (pin "DIODE_BIAS_2") (pinfunction "DIODE_BIAS_2_DIODE_BIAS_2") (pintype "input"))
    )
    (net (code "59") (name "Net-(R37-Pad2)") (class "Default")
      (node (ref "R37") (pin "2") (pinfunction "2_2") (pintype "passive"))
      (node (ref "U$5") (pin "+IN_2") (pinfunction "+IN_2_+IN_2") (pintype "input"))
      (node (ref "VCA_TRIM") (pin "E") (pinfunction "E_E") (pintype "passive"))
    )
    (net (code "60") (name "Net-(R38-Pad2)") (class "Default")
      (node (ref "R38") (pin "2") (pinfunction "2_2") (pintype "passive"))
      (node (ref "U$5") (pin "OUT_2") (pinfunction "OUT_2_OUT_2") (pintype "output"))
      (node (ref "U$6") (pin "+IN_2") (pinfunction "+IN_2_+IN_2") (pintype "input"))
    )
    (net (code "61") (name "Net-(R39-Pad1)") (class "Default")
      (node (ref "R39") (pin "1") (pinfunction "1_1") (pintype "passive"))
      (node (ref "U$7") (pin "DIODE_BIAS_1") (pinfunction "DIODE_BIAS_1_DIODE_BIAS_1") (pintype "input"))
    )
    (net (code "62") (name "Net-(U$2A-B)") (class "Default")
      (node (ref "R5") (pin "1") (pinfunction "1_1") (pintype "passive"))
      (node (ref "U$2") (pin "Q1_B") (pinfunction "B_Q1_B") (pintype "bidirectional"))
    )
    (net (code "63") (name "Net-(U$2A-C)") (class "Default")
      (node (ref "C1") (pin "2") (pinfunction "2_2") (pintype "passive"))
      (node (ref "R7") (pin "1") (pinfunction "1_1") (pintype "passive"))
      (node (ref "U$1") (pin "OUT_1") (pinfunction "OUT_1_OUT_1") (pintype "output"))
      (node (ref "U$2") (pin "Q1_C") (pinfunction "C_Q1_C") (pintype "bidirectional"))
    )
    (net (code "64") (name "Net-(U$2B-B)") (class "Default")
      (node (ref "D3") (pin "C") (pinfunction "C_C") (pintype "passive"))
      (node (ref "R24") (pin "1") (pinfunction "1_1") (pintype "passive"))
      (node (ref "U$2") (pin "Q2_B") (pinfunction "B_Q2_B") (pintype "bidirectional"))
      (node (ref "U$2") (pin "Q3_B") (pinfunction "B_Q3_B") (pintype "bidirectional"))
    )
    (net (code "65") (name "Net-(U$2B-C)") (class "Default")
      (node (ref "U$2") (pin "Q2_C") (pinfunction "C_Q2_C") (pintype "bidirectional"))
      (node (ref "U$4") (pin "AMP_BIAS_1") (pinfunction "AMP_BIAS_1_AMP_BIAS_1") (pintype "input"))
    )
    (net (code "66") (name "Net-(U$2B-E)") (class "Default")
      (node (ref "U$2") (pin "Q2_E") (pinfunction "E_Q2_E") (pintype "bidirectional"))
      (node (ref "U$2") (pin "Q3_E") (pinfunction "E_Q3_E") (pintype "bidirectional"))
      (node (ref "U$5") (pin "OUT_1") (pinfunction "OUT_1_OUT_1") (pintype "output"))
    )
    (net (code "67") (name "Net-(U$2C-C)") (class "Default")
      (node (ref "U$2") (pin "Q3_C") (pinfunction "C_Q3_C") (pintype "bidirectional"))
      (node (ref "U$4") (pin "AMP_BIAS_2") (pinfunction "AMP_BIAS_2_AMP_BIAS_2") (pintype "input"))
    )
    (net (code "68") (name "Net-(U$5-Pad-IN_2)") (class "Default")
      (node (ref "U$5") (pin "-IN_2") (pinfunction "-IN_2_-IN_2") (pintype "input"))
      (node (ref "VCA_TRIM") (pin "A") (pinfunction "A_A") (pintype "passive"))
    )
    (net (code "69") (name "Net-(U$5-PadAMP_BIAS_2)") (class "Default")
      (node (ref "U$5") (pin "AMP_BIAS_2") (pinfunction "AMP_BIAS_2_AMP_BIAS_2") (pintype "input"))
      (node (ref "U$7") (pin "OUT_1") (pinfunction "OUT_1_OUT_1") (pintype "output"))
    )
    (net (code "70") (name "Net-(U$7-Pad-IN_1)") (class "Default")
      (node (ref "U$7") (pin "-IN_1") (pinfunction "-IN_1_-IN_1") (pintype "input"))
      (node (ref "VCA_TRIM1") (pin "A") (pinfunction "A_A") (pintype "passive"))
    )
    (net (code "71") (name "unconnected-(IC1-DB-Pad9)") (class "Default")
      (node (ref "IC1") (pin "9") (pinfunction "DB_9") (pintype "passive"))
    )
    (net (code "72") (name "unconnected-(IC1-S1B-Pad13)") (class "Default")
      (node (ref "IC1") (pin "13") (pinfunction "S1B_13") (pintype "passive"))
    )
    (net (code "73") (name "unconnected-(IC1-S2B-Pad12)") (class "Default")
      (node (ref "IC1") (pin "12") (pinfunction "S2B_12") (pintype "passive"))
    )
    (net (code "74") (name "unconnected-(IC1-S3B-Pad11)") (class "Default")
      (node (ref "IC1") (pin "11") (pinfunction "S3B_11") (pintype "passive"))
    )
    (net (code "75") (name "unconnected-(IC1-S4B-Pad10)") (class "Default")
      (node (ref "IC1") (pin "10") (pinfunction "S4B_10") (pintype "passive"))
    )
    (net (code "76") (name "unconnected-(IC2-DB-Pad9)") (class "Default")
      (node (ref "IC2") (pin "9") (pinfunction "DB_9") (pintype "passive"))
    )
    (net (code "77") (name "unconnected-(IC2-S1B-Pad13)") (class "Default")
      (node (ref "IC2") (pin "13") (pinfunction "S1B_13") (pintype "passive"))
    )
    (net (code "78") (name "unconnected-(IC2-S2A-Pad5)") (class "Default")
      (node (ref "IC2") (pin "5") (pinfunction "S2A_5") (pintype "passive"))
    )
    (net (code "79") (name "unconnected-(IC2-S2B-Pad12)") (class "Default")
      (node (ref "IC2") (pin "12") (pinfunction "S2B_12") (pintype "passive"))
    )
    (net (code "80") (name "unconnected-(IC2-S3B-Pad11)") (class "Default")
      (node (ref "IC2") (pin "11") (pinfunction "S3B_11") (pintype "passive"))
    )
    (net (code "81") (name "unconnected-(IC2-S4B-Pad10)") (class "Default")
      (node (ref "IC2") (pin "10") (pinfunction "S4B_10") (pintype "passive"))
    )
    (net (code "82") (name "unconnected-(IC3-DB-Pad9)") (class "Default")
      (node (ref "IC3") (pin "9") (pinfunction "DB_9") (pintype "passive"))
    )
    (net (code "83") (name "unconnected-(IC3-S1B-Pad13)") (class "Default")
      (node (ref "IC3") (pin "13") (pinfunction "S1B_13") (pintype "passive"))
    )
    (net (code "84") (name "unconnected-(IC3-S2B-Pad12)") (class "Default")
      (node (ref "IC3") (pin "12") (pinfunction "S2B_12") (pintype "passive"))
    )
    (net (code "85") (name "unconnected-(IC3-S3B-Pad11)") (class "Default")
      (node (ref "IC3") (pin "11") (pinfunction "S3B_11") (pintype "passive"))
    )
    (net (code "86") (name "unconnected-(IC3-S4A-Pad7)") (class "Default")
      (node (ref "IC3") (pin "7") (pinfunction "S4A_7") (pintype "passive"))
    )
    (net (code "87") (name "unconnected-(IC3-S4B-Pad10)") (class "Default")
      (node (ref "IC3") (pin "10") (pinfunction "S4B_10") (pintype "passive"))
    )
    (net (code "88") (name "unconnected-(OSC_SUM_TRIM-PadE)") (class "Default")
      (node (ref "OSC_SUM_TRIM") (pin "E") (pinfunction "E_E") (pintype "passive"))
    )
    (net (code "89") (name "unconnected-(R40-Pad1)") (class "Default")
      (node (ref "R40") (pin "1") (pinfunction "1_1") (pintype "passive"))
    )
  )
)
